# Sheet1.net
KiCad netlist of a schematic drawn in Altium Designer
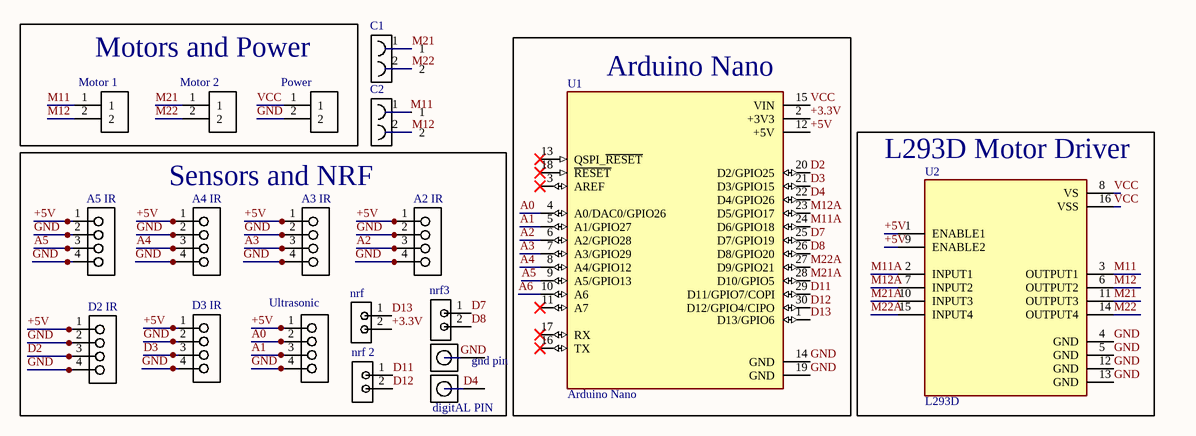
[diagram p0: Sheet1.SchDoc]

(export (version "E")
  (design (tool "Eeschema 10.0.6"))
  (components
    (comp (ref "A2 IR")
      (value "4pin jst")
      (footprint "4pin jst")
      (description "Connector Header Through Hole 4 position 0.079 (2.00mm)")
      (fields (field (name "MP") "B4B-PH-K") (field (name "MF") "JST"))
      (libsource (lib "Schlib1") (part "4pin jst"))
    )
    (comp (ref "A3 IR")
      (value "4pin jst")
      (footprint "4pin jst")
      (description "Connector Header Through Hole 4 position 0.079 (2.00mm)")
      (fields (field (name "MP") "B4B-PH-K") (field (name "MF") "JST"))
      (libsource (lib "Schlib1") (part "4pin jst"))
    )
    (comp (ref "A4 IR")
      (value "4pin jst")
      (footprint "4pin jst")
      (description "Connector Header Through Hole 4 position 0.079 (2.00mm)")
      (fields (field (name "MP") "B4B-PH-K") (field (name "MF") "JST"))
      (libsource (lib "Schlib1") (part "4pin jst"))
    )
    (comp (ref "A5 IR")
      (value "4pin jst")
      (footprint "4pin jst")
      (description "Connector Header Through Hole 4 position 0.079 (2.00mm)")
      (fields (field (name "MP") "B4B-PH-K") (field (name "MF") "JST"))
      (libsource (lib "Schlib1") (part "4pin jst"))
    )
    (comp (ref "C1")
      (value "Capacitor")
      (footprint "Capacitor")
      (libsource (lib "Schlib1") (part "Capacitor"))
    )
    (comp (ref "C2")
      (value "Capacitor")
      (footprint "Capacitor")
      (libsource (lib "Schlib1") (part "Capacitor"))
    )
    (comp (ref "D2 IR")
      (value "4pin jst")
      (footprint "4pin jst")
      (description "Connector Header Through Hole 4 position 0.079 (2.00mm)")
      (fields (field (name "MP") "B4B-PH-K") (field (name "MF") "JST"))
      (libsource (lib "Schlib1") (part "4pin jst"))
    )
    (comp (ref "D3 IR")
      (value "4pin jst")
      (footprint "4pin jst")
      (description "Connector Header Through Hole 4 position 0.079 (2.00mm)")
      (fields (field (name "MP") "B4B-PH-K") (field (name "MF") "JST"))
      (libsource (lib "Schlib1") (part "4pin jst"))
    )
    (comp (ref "digitAL PIN")
      (value "1 pin female header")
      (footprint "1 pin female header")
      (libsource (lib "Schlib1") (part "1 pin female header"))
    )
    (comp (ref "gnd pin")
      (value "1 pin female header")
      (footprint "1 pin female header")
      (libsource (lib "Schlib1") (part "1 pin female header"))
    )
    (comp (ref "Motor 1")
      (value "2pin terminal block")
      (footprint "2pin terminal block")
      (description "Connector Terminal Blocks Receptacle 2 Position 5.08mm Solder Straight Thru-Hole 13.5A/Contact")
      (fields (field (name "MP") "282837-2") (field (name "MF") "TE Connectivity"))
      (libsource (lib "Schlib1") (part "2pin terminal block"))
    )
    (comp (ref "Motor 2")
      (value "2pin terminal block")
      (footprint "2pin terminal block")
      (description "Connector Terminal Blocks Receptacle 2 Position 5.08mm Solder Straight Thru-Hole 13.5A/Contact")
      (fields (field (name "MP") "282837-2") (field (name "MF") "TE Connectivity"))
      (libsource (lib "Schlib1") (part "2pin terminal block"))
    )
    (comp (ref "nrf")
      (value "2 pin female header")
      (footprint "2 pin female header")
      (libsource (lib "Schlib1") (part "2 pin female header"))
    )
    (comp (ref "nrf 2")
      (value "2 pin female header")
      (footprint "2 pin female header")
      (libsource (lib "Schlib1") (part "2 pin female header"))
    )
    (comp (ref "nrf3")
      (value "2 pin female header")
      (footprint "2 pin female header")
      (libsource (lib "Schlib1") (part "2 pin female header"))
    )
    (comp (ref "Power")
      (value "2pin terminal block")
      (footprint "2pin terminal block")
      (description "Connector Terminal Blocks Receptacle 2 Position 5.08mm Solder Straight Thru-Hole 13.5A/Contact")
      (fields (field (name "MP") "282837-2") (field (name "MF") "TE Connectivity"))
      (libsource (lib "Schlib1") (part "2pin terminal block"))
    )
    (comp (ref "U1")
      (value "Arduino Nano")
      (footprint "Arduino Nano")
      (fields
        (field (name "MF") "Arduino")
        (field (name "DIGI-KEY_PART_NUMBER") "1050-ABX00053-ND")
        (field (name "MP") "ABX00053")
      )
      (libsource (lib "Schlib1") (part "Arduino Nano"))
    )
    (comp (ref "U2")
      (value "L293D")
      (footprint "L293D")
      (description "Bipolar Motor Driver - Parallel 16-PowerDIP")
      (fields (field (name "MF") "STMicroelectronics"))
      (libsource (lib "Schlib1") (part "L293D"))
    )
    (comp (ref "Ultrasonic")
      (value "4pin jst")
      (footprint "4pin jst")
      (description "Connector Header Through Hole 4 position 0.079 (2.00mm)")
      (fields (field (name "MP") "B4B-PH-K") (field (name "MF") "JST"))
      (libsource (lib "Schlib1") (part "4pin jst"))
    )
  )
  (nets
    (net (code "1") (name "/+3.3V") (class "Default")
      (node (ref "U1") (pin "2") (pinfunction "+3V3_2") (pintype "power_in"))
      (node (ref "nrf") (pin "2") (pinfunction "2_2") (pintype "passive"))
    )
    (net (code "2") (name "/+5V") (class "Default")
      (node (ref "A2 IR") (pin "1") (pinfunction "1_1") (pintype "passive"))
      (node (ref "A3 IR") (pin "1") (pinfunction "1_1") (pintype "passive"))
      (node (ref "A4 IR") (pin "1") (pinfunction "1_1") (pintype "passive"))
      (node (ref "A5 IR") (pin "1") (pinfunction "1_1") (pintype "passive"))
      (node (ref "D2 IR") (pin "1") (pinfunction "1_1") (pintype "passive"))
      (node (ref "D3 IR") (pin "1") (pinfunction "1_1") (pintype "passive"))
      (node (ref "U1") (pin "12") (pinfunction "+5V_12") (pintype "power_in"))
      (node (ref "U2") (pin "1") (pinfunction "ENABLE1_1") (pintype "passive"))
      (node (ref "U2") (pin "9") (pinfunction "ENABLE2_9") (pintype "passive"))
      (node (ref "Ultrasonic") (pin "1") (pinfunction "1_1") (pintype "passive"))
    )
    (net (code "3") (name "/A0") (class "Default")
      (node (ref "U1") (pin "4") (pinfunction "A0/DAC0/GPIO26_4") (pintype "bidirectional"))
      (node (ref "Ultrasonic") (pin "2") (pinfunction "2_2") (pintype "passive"))
    )
    (net (code "4") (name "/A1") (class "Default")
      (node (ref "U1") (pin "5") (pinfunction "A1/GPIO27_5") (pintype "bidirectional"))
      (node (ref "Ultrasonic") (pin "3") (pinfunction "3_3") (pintype "passive"))
    )
    (net (code "5") (name "/A2") (class "Default")
      (node (ref "A2 IR") (pin "3") (pinfunction "3_3") (pintype "passive"))
      (node (ref "U1") (pin "6") (pinfunction "A2/GPIO28_6") (pintype "bidirectional"))
    )
    (net (code "6") (name "/A3") (class "Default")
      (node (ref "A3 IR") (pin "3") (pinfunction "3_3") (pintype "passive"))
      (node (ref "U1") (pin "7") (pinfunction "A3/GPIO29_7") (pintype "bidirectional"))
    )
    (net (code "7") (name "/A4") (class "Default")
      (node (ref "A4 IR") (pin "3") (pinfunction "3_3") (pintype "passive"))
      (node (ref "U1") (pin "8") (pinfunction "A4/GPIO12_8") (pintype "bidirectional"))
    )
    (net (code "8") (name "/A5") (class "Default")
      (node (ref "A5 IR") (pin "3") (pinfunction "3_3") (pintype "passive"))
      (node (ref "U1") (pin "9") (pinfunction "A5/GPIO13_9") (pintype "bidirectional"))
    )
    (net (code "9") (name "/A6") (class "Default")
      (node (ref "U1") (pin "10") (pinfunction "A6_10") (pintype "bidirectional"))
    )
    (net (code "10") (name "/D2") (class "Default")
      (node (ref "D2 IR") (pin "3") (pinfunction "3_3") (pintype "passive"))
      (node (ref "U1") (pin "20") (pinfunction "D2/GPIO25_20") (pintype "bidirectional"))
    )
    (net (code "11") (name "/D3") (class "Default")
      (node (ref "D3 IR") (pin "3") (pinfunction "3_3") (pintype "passive"))
      (node (ref "U1") (pin "21") (pinfunction "D3/GPIO15_21") (pintype "bidirectional"))
    )
    (net (code "12") (name "/D4") (class "Default")
      (node (ref "U1") (pin "22") (pinfunction "D4/GPIO26_22") (pintype "bidirectional"))
      (node (ref "digitAL PIN") (pin "1") (pinfunction "1_1") (pintype "passive"))
    )
    (net (code "13") (name "/D7") (class "Default")
      (node (ref "U1") (pin "25") (pinfunction "D7/GPIO19_25") (pintype "bidirectional"))
      (node (ref "nrf3") (pin "1") (pinfunction "1_1") (pintype "passive"))
    )
    (net (code "14") (name "/D8") (class "Default")
      (node (ref "U1") (pin "26") (pinfunction "D8/GPIO20_26") (pintype "bidirectional"))
      (node (ref "nrf3") (pin "2") (pinfunction "2_2") (pintype "passive"))
    )
    (net (code "15") (name "/D11") (class "Default")
      (node (ref "U1") (pin "29") (pinfunction "D11/GPIO7/COPI_29") (pintype "bidirectional"))
      (node (ref "nrf 2") (pin "1") (pinfunction "1_1") (pintype "passive"))
    )
    (net (code "16") (name "/D12") (class "Default")
      (node (ref "U1") (pin "30") (pinfunction "D12/GPIO4/CIPO_30") (pintype "bidirectional"))
      (node (ref "nrf 2") (pin "2") (pinfunction "2_2") (pintype "passive"))
    )
    (net (code "17") (name "/D13") (class "Default")
      (node (ref "U1") (pin "1") (pinfunction "D13/GPIO6_1") (pintype "bidirectional"))
      (node (ref "nrf") (pin "1") (pinfunction "1_1") (pintype "passive"))
    )
    (net (code "18") (name "/GND") (class "Default")
      (node (ref "A2 IR") (pin "2") (pinfunction "2_2") (pintype "passive"))
      (node (ref "A2 IR") (pin "4") (pinfunction "4_4") (pintype "passive"))
      (node (ref "A3 IR") (pin "2") (pinfunction "2_2") (pintype "passive"))
      (node (ref "A3 IR") (pin "4") (pinfunction "4_4") (pintype "passive"))
      (node (ref "A4 IR") (pin "2") (pinfunction "2_2") (pintype "passive"))
      (node (ref "A4 IR") (pin "4") (pinfunction "4_4") (pintype "passive"))
      (node (ref "A5 IR") (pin "2") (pinfunction "2_2") (pintype "passive"))
      (node (ref "A5 IR") (pin "4") (pinfunction "4_4") (pintype "passive"))
      (node (ref "D2 IR") (pin "2") (pinfunction "2_2") (pintype "passive"))
      (node (ref "D2 IR") (pin "4") (pinfunction "4_4") (pintype "passive"))
      (node (ref "D3 IR") (pin "2") (pinfunction "2_2") (pintype "passive"))
      (node (ref "D3 IR") (pin "4") (pinfunction "4_4") (pintype "passive"))
      (node (ref "Power") (pin "2") (pinfunction "2_2") (pintype "passive"))
      (node (ref "U1") (pin "14") (pinfunction "GND_14") (pintype "power_in"))
      (node (ref "U1") (pin "19") (pinfunction "GND_19") (pintype "power_in"))
      (node (ref "U2") (pin "12") (pinfunction "GND_12") (pintype "power_in"))
      (node (ref "U2") (pin "13") (pinfunction "GND_13") (pintype "power_in"))
      (node (ref "U2") (pin "4") (pinfunction "GND_4") (pintype "power_in"))
      (node (ref "U2") (pin "5") (pinfunction "GND_5") (pintype "power_in"))
      (node (ref "Ultrasonic") (pin "4") (pinfunction "4_4") (pintype "passive"))
      (node (ref "gnd pin") (pin "1") (pinfunction "1_1") (pintype "passive"))
    )
    (net (code "19") (name "/M11") (class "Default")
      (node (ref "C2") (pin "1") (pinfunction "1_1") (pintype "passive"))
      (node (ref "Motor 1") (pin "1") (pinfunction "1_1") (pintype "passive"))
      (node (ref "U2") (pin "3") (pinfunction "OUTPUT1_3") (pintype "passive"))
    )
    (net (code "20") (name "/M11A") (class "Default")
      (node (ref "U1") (pin "24") (pinfunction "D6/GPIO18_24") (pintype "bidirectional"))
      (node (ref "U2") (pin "2") (pinfunction "INPUT1_2") (pintype "passive"))
    )
    (net (code "21") (name "/M12") (class "Default")
      (node (ref "C2") (pin "2") (pinfunction "2_2") (pintype "passive"))
      (node (ref "Motor 1") (pin "2") (pinfunction "2_2") (pintype "passive"))
      (node (ref "U2") (pin "6") (pinfunction "OUTPUT2_6") (pintype "passive"))
    )
    (net (code "22") (name "/M12A") (class "Default")
      (node (ref "U1") (pin "23") (pinfunction "D5/GPIO17_23") (pintype "bidirectional"))
      (node (ref "U2") (pin "7") (pinfunction "INPUT2_7") (pintype "passive"))
    )
    (net (code "23") (name "/M21") (class "Default")
      (node (ref "C1") (pin "1") (pinfunction "1_1") (pintype "passive"))
      (node (ref "Motor 2") (pin "1") (pinfunction "1_1") (pintype "passive"))
      (node (ref "U2") (pin "11") (pinfunction "OUTPUT3_11") (pintype "passive"))
    )
    (net (code "24") (name "/M21A") (class "Default")
      (node (ref "U1") (pin "28") (pinfunction "D10/GPIO5_28") (pintype "bidirectional"))
      (node (ref "U2") (pin "10") (pinfunction "INPUT3_10") (pintype "passive"))
    )
    (net (code "25") (name "/M22") (class "Default")
      (node (ref "C1") (pin "2") (pinfunction "2_2") (pintype "passive"))
      (node (ref "Motor 2") (pin "2") (pinfunction "2_2") (pintype "passive"))
      (node (ref "U2") (pin "14") (pinfunction "OUTPUT4_14") (pintype "passive"))
    )
    (net (code "26") (name "/M22A") (class "Default")
      (node (ref "U1") (pin "27") (pinfunction "D9/GPIO21_27") (pintype "bidirectional"))
      (node (ref "U2") (pin "15") (pinfunction "INPUT4_15") (pintype "passive"))
    )
    (net (code "27") (name "/VCC") (class "Default")
      (node (ref "Power") (pin "1") (pinfunction "1_1") (pintype "passive"))
      (node (ref "U1") (pin "15") (pinfunction "VIN_15") (pintype "power_in"))
      (node (ref "U2") (pin "16") (pinfunction "VSS_16") (pintype "power_in"))
      (node (ref "U2") (pin "8") (pinfunction "VS_8") (pintype "power_in"))
    )
    (net (code "28") (name "unconnected-(U1-A7-Pad11)") (class "Default")
      (node (ref "U1") (pin "11") (pinfunction "A7_11") (pintype "bidirectional+no_connect"))
    )
    (net (code "29") (name "unconnected-(U1-AREF-Pad3)") (class "Default")
      (node (ref "U1") (pin "3") (pinfunction "AREF_3") (pintype "bidirectional+no_connect"))
    )
    (net (code "30") (name "unconnected-(U1-QSPI_~{RESET}-Pad13)") (class "Default")
      (node (ref "U1") (pin "13") (pinfunction "QSPI_~{RESET}_13") (pintype "input+no_connect"))
    )
    (net (code "31") (name "unconnected-(U1-RX-Pad17)") (class "Default")
      (node (ref "U1") (pin "17") (pinfunction "RX_17") (pintype "bidirectional+no_connect"))
    )
    (net (code "32") (name "unconnected-(U1-TX-Pad16)") (class "Default")
      (node (ref "U1") (pin "16") (pinfunction "TX_16") (pintype "bidirectional+no_connect"))
    )
    (net (code "33") (name "unconnected-(U1-~{RESET}-Pad18)") (class "Default")
      (node (ref "U1") (pin "18") (pinfunction "~{RESET}_18") (pintype "input+no_connect"))
    )
  )
)
